# pyboard.net
KiCad netlist of a schematic drawn in Altium Designer
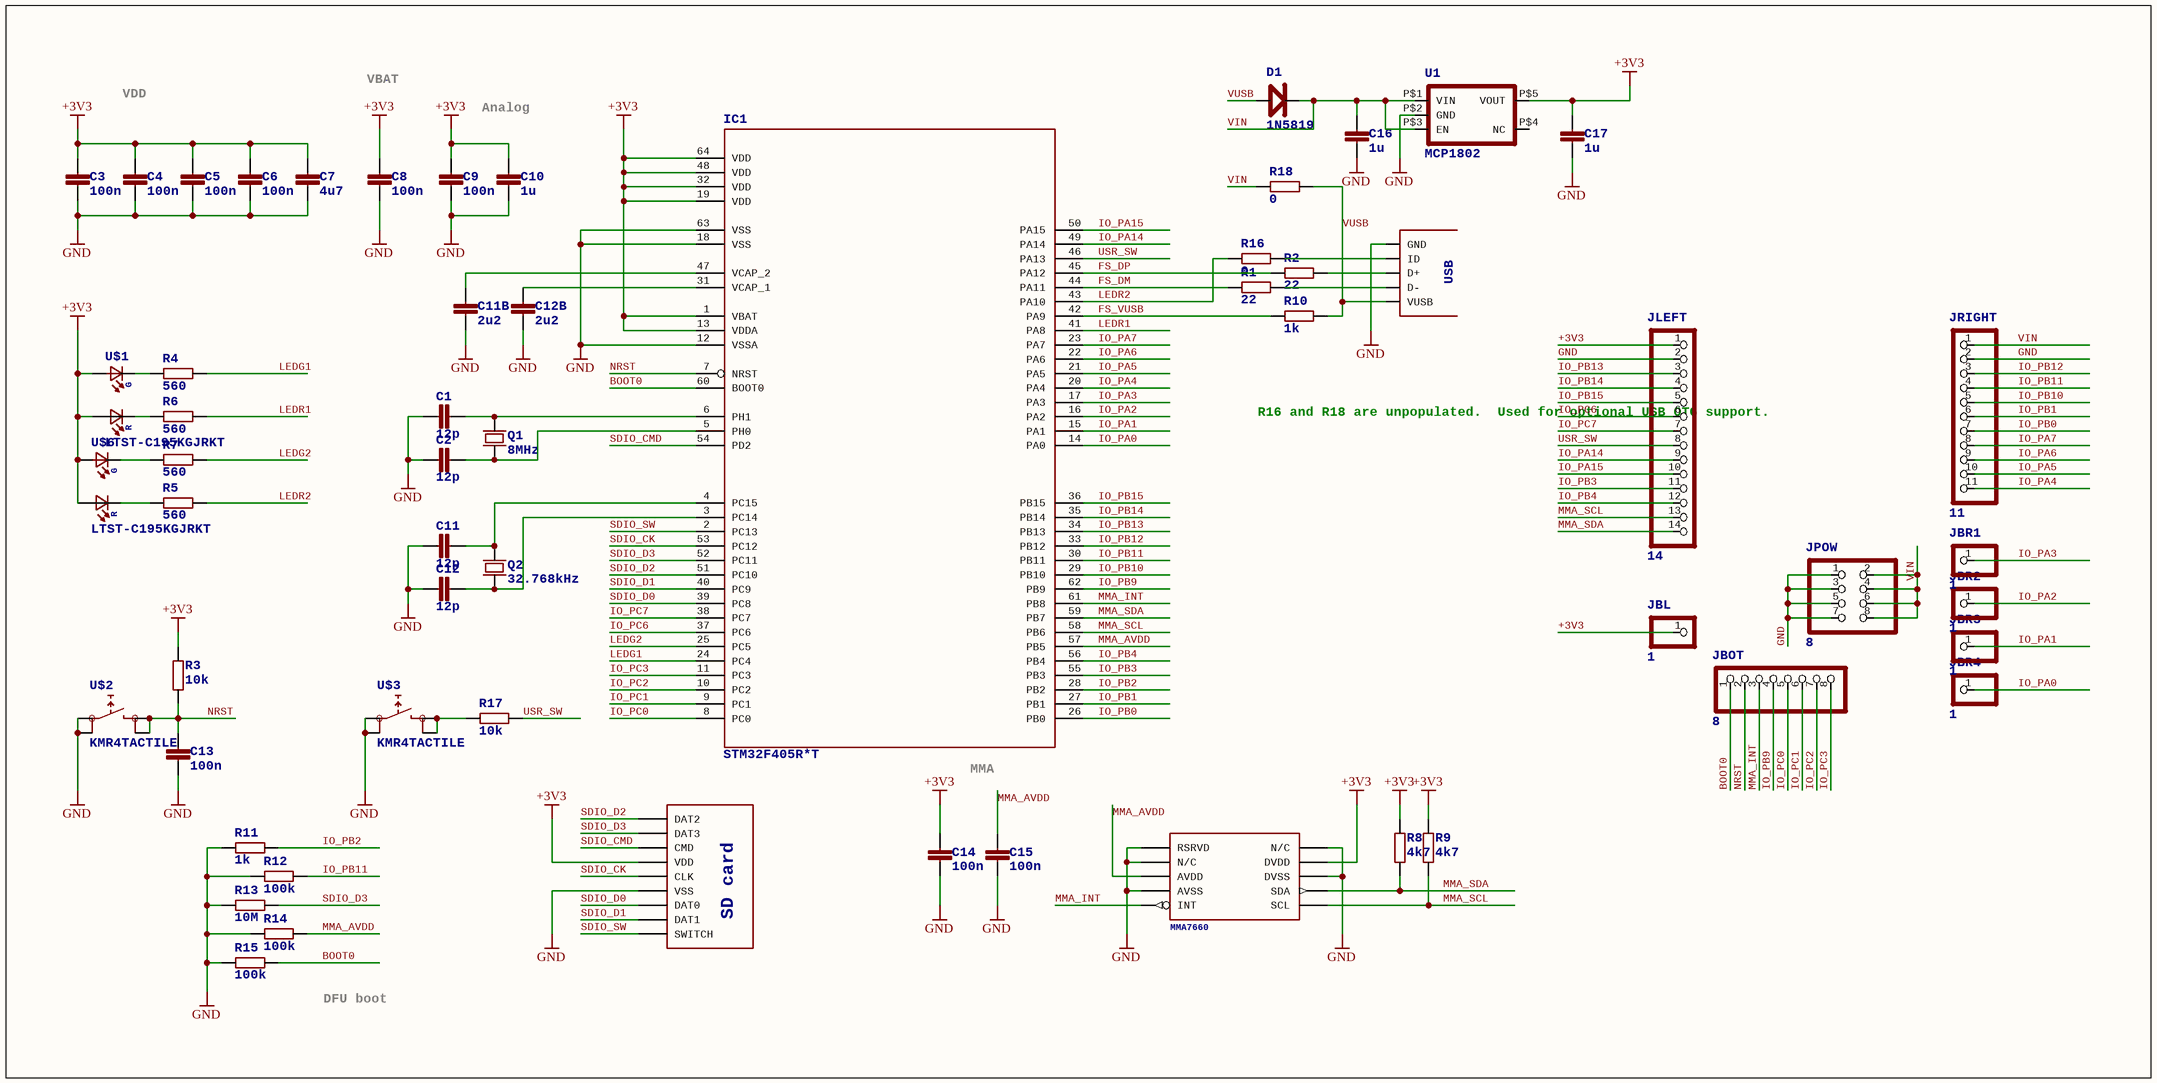
[diagram p0: pyboard.SchDoc]

(export (version "E")
  (design (tool "Eeschema 10.0.6"))
  (components
    (comp (ref "C1")
      (value "12p")
      (footprint "C0603")
      (description "CAPACITOR, European symbol")
      (libsource (lib "") (part "C-EUC0603_1"))
    )
    (comp (ref "C2")
      (value "12p")
      (footprint "C0603")
      (description "CAPACITOR, European symbol")
      (libsource (lib "") (part "C-EUC0603_1"))
    )
    (comp (ref "C3")
      (value "100n")
      (footprint "C0603")
      (description "CAPACITOR, European symbol")
      (libsource (lib "rcl") (part "C-EUC0603"))
    )
    (comp (ref "C4")
      (value "100n")
      (footprint "C0603")
      (description "CAPACITOR, European symbol")
      (libsource (lib "rcl") (part "C-EUC0603"))
    )
    (comp (ref "C5")
      (value "100n")
      (footprint "C0603")
      (description "CAPACITOR, European symbol")
      (libsource (lib "rcl") (part "C-EUC0603"))
    )
    (comp (ref "C6")
      (value "100n")
      (footprint "C0603")
      (description "CAPACITOR, European symbol")
      (libsource (lib "rcl") (part "C-EUC0603"))
    )
    (comp (ref "C7")
      (value "4u7")
      (footprint "C0603")
      (description "CAPACITOR, European symbol")
      (libsource (lib "rcl") (part "C-EUC0603"))
    )
    (comp (ref "C8")
      (value "100n")
      (footprint "C0603")
      (description "CAPACITOR, European symbol")
      (libsource (lib "rcl") (part "C-EUC0603"))
    )
    (comp (ref "C9")
      (value "100n")
      (footprint "C0603")
      (description "CAPACITOR, European symbol")
      (libsource (lib "rcl") (part "C-EUC0603"))
    )
    (comp (ref "C10")
      (value "1u")
      (footprint "C0603")
      (description "CAPACITOR, European symbol")
      (libsource (lib "rcl") (part "C-EUC0603"))
    )
    (comp (ref "C11")
      (value "12p")
      (footprint "C0603")
      (description "CAPACITOR, European symbol")
      (libsource (lib "") (part "C-EUC0603_1"))
    )
    (comp (ref "C11B")
      (value "2u2")
      (footprint "C0603")
      (description "CAPACITOR, European symbol")
      (libsource (lib "rcl") (part "C-EUC0603"))
    )
    (comp (ref "C12")
      (value "12p")
      (footprint "C0603")
      (description "CAPACITOR, European symbol")
      (libsource (lib "") (part "C-EUC0603_1"))
    )
    (comp (ref "C12B")
      (value "2u2")
      (footprint "C0603")
      (description "CAPACITOR, European symbol")
      (libsource (lib "rcl") (part "C-EUC0603"))
    )
    (comp (ref "C13")
      (value "100n")
      (footprint "C0603")
      (description "CAPACITOR, European symbol")
      (libsource (lib "rcl") (part "C-EUC0603"))
    )
    (comp (ref "C14")
      (value "100n")
      (footprint "C0603")
      (description "CAPACITOR, European symbol")
      (libsource (lib "rcl") (part "C-EUC0603"))
    )
    (comp (ref "C15")
      (value "100n")
      (footprint "C0603")
      (description "CAPACITOR, European symbol")
      (libsource (lib "rcl") (part "C-EUC0603"))
    )
    (comp (ref "C16")
      (value "1u")
      (footprint "C0603")
      (description "CAPACITOR, European symbol")
      (libsource (lib "rcl") (part "C-EUC0603"))
    )
    (comp (ref "C17")
      (value "1u")
      (footprint "C0603")
      (description "CAPACITOR, European symbol")
      (libsource (lib "rcl") (part "C-EUC0603"))
    )
    (comp (ref "D1") (value "1N5819") (footprint "SOD-123") (libsource (lib "pyboard") (part "1N5819")))
    (comp (ref "IC1")
      (value "STM32F405R*T")
      (footprint "LQFP64")
      (libsource (lib "pyboard") (part "STM32F405R*T"))
    )
    (comp (ref "JBL")
      (value "1")
      (footprint "1X01")
      (description "PIN HEADER")
      (libsource (lib "pinhead") (part "PINHD-1X1"))
    )
    (comp (ref "JBOT")
      (value "8")
      (footprint "1X08")
      (description "PIN HEADER")
      (libsource (lib "pinhead") (part "PINHD-1X8"))
    )
    (comp (ref "JBR1")
      (value "1")
      (footprint "1X01")
      (description "PIN HEADER")
      (libsource (lib "pinhead") (part "PINHD-1X1"))
    )
    (comp (ref "JBR2")
      (value "1")
      (footprint "1X01")
      (description "PIN HEADER")
      (libsource (lib "pinhead") (part "PINHD-1X1"))
    )
    (comp (ref "JBR3")
      (value "1")
      (footprint "1X01")
      (description "PIN HEADER")
      (libsource (lib "pinhead") (part "PINHD-1X1"))
    )
    (comp (ref "JBR4")
      (value "1")
      (footprint "1X01")
      (description "PIN HEADER")
      (libsource (lib "pinhead") (part "PINHD-1X1"))
    )
    (comp (ref "JLEFT")
      (value "14")
      (footprint "1X14")
      (description "PIN HEADER")
      (libsource (lib "pinhead") (part "PINHD-1X14"))
    )
    (comp (ref "JPOW")
      (value "8")
      (footprint "2X04")
      (description "PIN HEADER")
      (libsource (lib "pinhead") (part "PINHD-2X4"))
    )
    (comp (ref "JRIGHT")
      (value "11")
      (footprint "1X11")
      (description "PIN HEADER")
      (libsource (lib "pinhead") (part "PINHD-1X11"))
    )
    (comp (ref "Q1")
      (value "8MHz")
      (footprint "TXC-SMD-50X32")
      (libsource (lib "pyboard") (part "TXC-CRYSTAL50X32"))
    )
    (comp (ref "Q2")
      (value "32.768kHz")
      (footprint "TXC-SMD-32X15")
      (libsource (lib "pyboard") (part "TXC-CRYSTAL32X15"))
    )
    (comp (ref "R1")
      (value "22")
      (footprint "R0603")
      (description "RESISTOR, European symbol")
      (libsource (lib "rcl") (part "R-EU_R0603"))
    )
    (comp (ref "R2")
      (value "22")
      (footprint "R0603")
      (description "RESISTOR, European symbol")
      (libsource (lib "rcl") (part "R-EU_R0603"))
    )
    (comp (ref "R3")
      (value "10k")
      (footprint "R0603")
      (description "RESISTOR, European symbol")
      (libsource (lib "rcl") (part "R-EU_R0603"))
    )
    (comp (ref "R4")
      (value "560")
      (footprint "R0603")
      (description "RESISTOR, European symbol")
      (libsource (lib "rcl") (part "R-EU_R0603"))
    )
    (comp (ref "R5")
      (value "560")
      (footprint "R0603")
      (description "RESISTOR, European symbol")
      (libsource (lib "rcl") (part "R-EU_R0603"))
    )
    (comp (ref "R6")
      (value "560")
      (footprint "R0603")
      (description "RESISTOR, European symbol")
      (libsource (lib "rcl") (part "R-EU_R0603"))
    )
    (comp (ref "R7")
      (value "560")
      (footprint "R0603")
      (description "RESISTOR, European symbol")
      (libsource (lib "rcl") (part "R-EU_R0603"))
    )
    (comp (ref "R8")
      (value "4k7")
      (footprint "R0603")
      (description "RESISTOR, European symbol")
      (libsource (lib "rcl") (part "R-EU_R0603"))
    )
    (comp (ref "R9")
      (value "4k7")
      (footprint "R0603")
      (description "RESISTOR, European symbol")
      (libsource (lib "rcl") (part "R-EU_R0603"))
    )
    (comp (ref "R10")
      (value "1k")
      (footprint "R0603")
      (description "RESISTOR, European symbol")
      (libsource (lib "rcl") (part "R-EU_R0603"))
    )
    (comp (ref "R11")
      (value "1k")
      (footprint "R0603")
      (description "RESISTOR, European symbol")
      (libsource (lib "rcl") (part "R-EU_R0603"))
    )
    (comp (ref "R12")
      (value "100k")
      (footprint "R0603")
      (description "RESISTOR, European symbol")
      (libsource (lib "rcl") (part "R-EU_R0603"))
    )
    (comp (ref "R13")
      (value "10M")
      (footprint "R0603")
      (description "RESISTOR, European symbol")
      (libsource (lib "rcl") (part "R-EU_R0603"))
    )
    (comp (ref "R14")
      (value "100k")
      (footprint "R0603")
      (description "RESISTOR, European symbol")
      (libsource (lib "rcl") (part "R-EU_R0603"))
    )
    (comp (ref "R15")
      (value "100k")
      (footprint "R0603")
      (description "RESISTOR, European symbol")
      (libsource (lib "rcl") (part "R-EU_R0603"))
    )
    (comp (ref "R16")
      (value "0")
      (footprint "R0603")
      (description "RESISTOR, European symbol")
      (libsource (lib "rcl") (part "R-EU_R0603"))
    )
    (comp (ref "R17")
      (value "10k")
      (footprint "R0603")
      (description "RESISTOR, European symbol")
      (libsource (lib "rcl") (part "R-EU_R0603"))
    )
    (comp (ref "R18")
      (value "0")
      (footprint "R0805")
      (description "RESISTOR, European symbol")
      (libsource (lib "rcl") (part "R-EU_R0805"))
    )
    (comp (ref "U$1")
      (value "LTST-C195KGJRKT")
      (footprint "LTST-BILED-15X16")
      (fields (field (name "R") "R") (field (name "G") "G"))
      (libsource (lib "pyboard") (part "LTST-C195KGJRKT"))
    )
    (comp (ref "U$2")
      (value "KMR4TACTILE")
      (footprint "KMR4SWITCH")
      (libsource (lib "pyboard") (part "KMR4TACTILE"))
    )
    (comp (ref "U$3")
      (value "KMR4TACTILE")
      (footprint "KMR4SWITCH")
      (libsource (lib "pyboard") (part "KMR4TACTILE"))
    )
    (comp (ref "U$4")
      (value "MOLEX-SD-105027")
      (footprint "MOLEX-SD-105027-PKG")
      (fields (field (name "SDCARD") "SD card"))
      (libsource (lib "pyboard") (part "MOLEX-SD-105027"))
    )
    (comp (ref "U$5")
      (value "MMA7660")
      (footprint "DFN10")
      (fields (field (name "MMA7660") "MMA7660"))
      (libsource (lib "pyboard") (part "MMA7660"))
    )
    (comp (ref "U$6")
      (value "LTST-C195KGJRKT")
      (footprint "LTST-BILED-15X16")
      (fields (field (name "R") "R") (field (name "G") "G"))
      (libsource (lib "pyboard") (part "LTST-C195KGJRKT"))
    )
    (comp (ref "U$7")
      (value "USB-MICRO-AB")
      (footprint "HRS-USB-ZX62D-AB-5P8-PKG")
      (fields (field (name "USB") "USB"))
      (libsource (lib "pyboard") (part "USB-MICRO-AB"))
    )
    (comp (ref "U1") (value "MCP1802") (footprint "SOT-23-5") (libsource (lib "pyboard") (part "MCP1802")))
  )
  (nets
    (net (code "1") (name "+3V3") (class "Default")
      (node (ref "C10") (pin "1") (pinfunction "1_1") (pintype "passive"))
      (node (ref "C14") (pin "1") (pinfunction "1_1") (pintype "passive"))
      (node (ref "C17") (pin "1") (pinfunction "1_1") (pintype "passive"))
      (node (ref "C3") (pin "1") (pinfunction "1_1") (pintype "passive"))
      (node (ref "C4") (pin "1") (pinfunction "1_1") (pintype "passive"))
      (node (ref "C5") (pin "1") (pinfunction "1_1") (pintype "passive"))
      (node (ref "C6") (pin "1") (pinfunction "1_1") (pintype "passive"))
      (node (ref "C7") (pin "1") (pinfunction "1_1") (pintype "passive"))
      (node (ref "C8") (pin "1") (pinfunction "1_1") (pintype "passive"))
      (node (ref "C9") (pin "1") (pinfunction "1_1") (pintype "passive"))
      (node (ref "IC1") (pin "1") (pinfunction "VBAT_1") (pintype "power_in"))
      (node (ref "IC1") (pin "13") (pinfunction "VDDA_13") (pintype "power_in"))
      (node (ref "IC1") (pin "19") (pinfunction "VDD_19") (pintype "power_in"))
      (node (ref "IC1") (pin "32") (pinfunction "VDD_32") (pintype "power_in"))
      (node (ref "IC1") (pin "48") (pinfunction "VDD_48") (pintype "power_in"))
      (node (ref "IC1") (pin "64") (pinfunction "VDD_64") (pintype "power_in"))
      (node (ref "JBL") (pin "1") (pinfunction "1_1") (pintype "passive"))
      (node (ref "JLEFT") (pin "1") (pinfunction "1_1") (pintype "passive"))
      (node (ref "R3") (pin "1") (pinfunction "1_1") (pintype "passive"))
      (node (ref "R8") (pin "1") (pinfunction "1_1") (pintype "passive"))
      (node (ref "R9") (pin "1") (pinfunction "1_1") (pintype "passive"))
      (node (ref "U$1") (pin "P$1") (pinfunction "A1_P$1") (pintype "passive"))
      (node (ref "U$1") (pin "P$2") (pinfunction "A2_P$2") (pintype "passive"))
      (node (ref "U$4") (pin "P$4") (pinfunction "VDD_P$4") (pintype "passive"))
      (node (ref "U$5") (pin "P$9") (pinfunction "DVDD_P$9") (pintype "power_in"))
      (node (ref "U$6") (pin "P$1") (pinfunction "A1_P$1") (pintype "passive"))
      (node (ref "U$6") (pin "P$2") (pinfunction "A2_P$2") (pintype "passive"))
      (node (ref "U1") (pin "P$5") (pinfunction "VOUT_P$5") (pintype "power_in"))
    )
    (net (code "2") (name "/BOOT0") (class "Default")
      (node (ref "IC1") (pin "60") (pinfunction "BOOT0_60") (pintype "passive"))
      (node (ref "JBOT") (pin "1") (pinfunction "1_1") (pintype "passive"))
      (node (ref "R15") (pin "1") (pinfunction "1_1") (pintype "passive"))
    )
    (net (code "3") (name "/FS_DM") (class "Default")
      (node (ref "IC1") (pin "44") (pinfunction "PA11_44") (pintype "passive"))
      (node (ref "R1") (pin "2") (pinfunction "2_2") (pintype "passive"))
    )
    (net (code "4") (name "/FS_DP") (class "Default")
      (node (ref "IC1") (pin "45") (pinfunction "PA12_45") (pintype "passive"))
      (node (ref "R2") (pin "2") (pinfunction "2_2") (pintype "passive"))
    )
    (net (code "5") (name "/FS_VUSB") (class "Default")
      (node (ref "IC1") (pin "42") (pinfunction "PA9_42") (pintype "passive"))
      (node (ref "R10") (pin "2") (pinfunction "2_2") (pintype "passive"))
    )
    (net (code "6") (name "/IO_PA0") (class "Default")
      (node (ref "IC1") (pin "14") (pinfunction "PA0_14") (pintype "passive"))
      (node (ref "JBR4") (pin "1") (pinfunction "1_1") (pintype "passive"))
    )
    (net (code "7") (name "/IO_PA1") (class "Default")
      (node (ref "IC1") (pin "15") (pinfunction "PA1_15") (pintype "passive"))
      (node (ref "JBR3") (pin "1") (pinfunction "1_1") (pintype "passive"))
    )
    (net (code "8") (name "/IO_PA2") (class "Default")
      (node (ref "IC1") (pin "16") (pinfunction "PA2_16") (pintype "passive"))
      (node (ref "JBR2") (pin "1") (pinfunction "1_1") (pintype "passive"))
    )
    (net (code "9") (name "/IO_PA3") (class "Default")
      (node (ref "IC1") (pin "17") (pinfunction "PA3_17") (pintype "passive"))
      (node (ref "JBR1") (pin "1") (pinfunction "1_1") (pintype "passive"))
    )
    (net (code "10") (name "/IO_PA4") (class "Default")
      (node (ref "IC1") (pin "20") (pinfunction "PA4_20") (pintype "passive"))
      (node (ref "JRIGHT") (pin "11") (pinfunction "11_11") (pintype "passive"))
    )
    (net (code "11") (name "/IO_PA5") (class "Default")
      (node (ref "IC1") (pin "21") (pinfunction "PA5_21") (pintype "passive"))
      (node (ref "JRIGHT") (pin "10") (pinfunction "10_10") (pintype "passive"))
    )
    (net (code "12") (name "/IO_PA6") (class "Default")
      (node (ref "IC1") (pin "22") (pinfunction "PA6_22") (pintype "passive"))
      (node (ref "JRIGHT") (pin "9") (pinfunction "9_9") (pintype "passive"))
    )
    (net (code "13") (name "/IO_PA7") (class "Default")
      (node (ref "IC1") (pin "23") (pinfunction "PA7_23") (pintype "passive"))
      (node (ref "JRIGHT") (pin "8") (pinfunction "8_8") (pintype "passive"))
    )
    (net (code "14") (name "/IO_PA14") (class "Default")
      (node (ref "IC1") (pin "49") (pinfunction "PA14_49") (pintype "passive"))
      (node (ref "JLEFT") (pin "9") (pinfunction "9_9") (pintype "passive"))
    )
    (net (code "15") (name "/IO_PA15") (class "Default")
      (node (ref "IC1") (pin "50") (pinfunction "PA15_50") (pintype "passive"))
      (node (ref "JLEFT") (pin "10") (pinfunction "10_10") (pintype "passive"))
    )
    (net (code "16") (name "/IO_PB0") (class "Default")
      (node (ref "IC1") (pin "26") (pinfunction "PB0_26") (pintype "passive"))
      (node (ref "JRIGHT") (pin "7") (pinfunction "7_7") (pintype "passive"))
    )
    (net (code "17") (name "/IO_PB1") (class "Default")
      (node (ref "IC1") (pin "27") (pinfunction "PB1_27") (pintype "passive"))
      (node (ref "JRIGHT") (pin "6") (pinfunction "6_6") (pintype "passive"))
    )
    (net (code "18") (name "/IO_PB2") (class "Default")
      (node (ref "IC1") (pin "28") (pinfunction "PB2_28") (pintype "passive"))
      (node (ref "R11") (pin "1") (pinfunction "1_1") (pintype "passive"))
    )
    (net (code "19") (name "/IO_PB3") (class "Default")
      (node (ref "IC1") (pin "55") (pinfunction "PB3_55") (pintype "passive"))
      (node (ref "JLEFT") (pin "11") (pinfunction "11_11") (pintype "passive"))
    )
    (net (code "20") (name "/IO_PB4") (class "Default")
      (node (ref "IC1") (pin "56") (pinfunction "PB4_56") (pintype "passive"))
      (node (ref "JLEFT") (pin "12") (pinfunction "12_12") (pintype "passive"))
    )
    (net (code "21") (name "/IO_PB9") (class "Default")
      (node (ref "IC1") (pin "62") (pinfunction "PB9_62") (pintype "passive"))
      (node (ref "JBOT") (pin "4") (pinfunction "4_4") (pintype "passive"))
    )
    (net (code "22") (name "/IO_PB10") (class "Default")
      (node (ref "IC1") (pin "29") (pinfunction "PB10_29") (pintype "passive"))
      (node (ref "JRIGHT") (pin "5") (pinfunction "5_5") (pintype "passive"))
    )
    (net (code "23") (name "/IO_PB11") (class "Default")
      (node (ref "IC1") (pin "30") (pinfunction "PB11_30") (pintype "passive"))
      (node (ref "JRIGHT") (pin "4") (pinfunction "4_4") (pintype "passive"))
      (node (ref "R12") (pin "1") (pinfunction "1_1") (pintype "passive"))
    )
    (net (code "24") (name "/IO_PB12") (class "Default")
      (node (ref "IC1") (pin "33") (pinfunction "PB12_33") (pintype "passive"))
      (node (ref "JRIGHT") (pin "3") (pinfunction "3_3") (pintype "passive"))
    )
    (net (code "25") (name "/IO_PB13") (class "Default")
      (node (ref "IC1") (pin "34") (pinfunction "PB13_34") (pintype "passive"))
      (node (ref "JLEFT") (pin "3") (pinfunction "3_3") (pintype "passive"))
    )
    (net (code "26") (name "/IO_PB14") (class "Default")
      (node (ref "IC1") (pin "35") (pinfunction "PB14_35") (pintype "passive"))
      (node (ref "JLEFT") (pin "4") (pinfunction "4_4") (pintype "passive"))
    )
    (net (code "27") (name "/IO_PB15") (class "Default")
      (node (ref "IC1") (pin "36") (pinfunction "PB15_36") (pintype "passive"))
      (node (ref "JLEFT") (pin "5") (pinfunction "5_5") (pintype "passive"))
    )
    (net (code "28") (name "/IO_PC0") (class "Default")
      (node (ref "IC1") (pin "8") (pinfunction "PC0_8") (pintype "passive"))
      (node (ref "JBOT") (pin "5") (pinfunction "5_5") (pintype "passive"))
    )
    (net (code "29") (name "/IO_PC1") (class "Default")
      (node (ref "IC1") (pin "9") (pinfunction "PC1_9") (pintype "passive"))
      (node (ref "JBOT") (pin "6") (pinfunction "6_6") (pintype "passive"))
    )
    (net (code "30") (name "/IO_PC2") (class "Default")
      (node (ref "IC1") (pin "10") (pinfunction "PC2_10") (pintype "passive"))
      (node (ref "JBOT") (pin "7") (pinfunction "7_7") (pintype "passive"))
    )
    (net (code "31") (name "/IO_PC3") (class "Default")
      (node (ref "IC1") (pin "11") (pinfunction "PC3_11") (pintype "passive"))
      (node (ref "JBOT") (pin "8") (pinfunction "8_8") (pintype "passive"))
    )
    (net (code "32") (name "/IO_PC6") (class "Default")
      (node (ref "IC1") (pin "37") (pinfunction "PC6_37") (pintype "passive"))
      (node (ref "JLEFT") (pin "6") (pinfunction "6_6") (pintype "passive"))
    )
    (net (code "33") (name "/IO_PC7") (class "Default")
      (node (ref "IC1") (pin "38") (pinfunction "PC7_38") (pintype "passive"))
      (node (ref "JLEFT") (pin "7") (pinfunction "7_7") (pintype "passive"))
    )
    (net (code "34") (name "/LEDG1") (class "Default")
      (node (ref "IC1") (pin "24") (pinfunction "PC4_24") (pintype "passive"))
      (node (ref "R4") (pin "1") (pinfunction "1_1") (pintype "passive"))
    )
    (net (code "35") (name "/LEDG2") (class "Default")
      (node (ref "IC1") (pin "25") (pinfunction "PC5_25") (pintype "passive"))
      (node (ref "R7") (pin "1") (pinfunction "1_1") (pintype "passive"))
    )
    (net (code "36") (name "/LEDR1") (class "Default")
      (node (ref "IC1") (pin "41") (pinfunction "PA8_41") (pintype "passive"))
      (node (ref "R6") (pin "1") (pinfunction "1_1") (pintype "passive"))
    )
    (net (code "37") (name "/LEDR2") (class "Default")
      (node (ref "IC1") (pin "43") (pinfunction "PA10_43") (pintype "passive"))
      (node (ref "R16") (pin "2") (pinfunction "2_2") (pintype "passive"))
      (node (ref "R5") (pin "1") (pinfunction "1_1") (pintype "passive"))
    )
    (net (code "38") (name "/MMA_AVDD") (class "Default")
      (node (ref "C15") (pin "1") (pinfunction "1_1") (pintype "passive"))
      (node (ref "IC1") (pin "57") (pinfunction "PB5_57") (pintype "passive"))
      (node (ref "R14") (pin "1") (pinfunction "1_1") (pintype "passive"))
      (node (ref "U$5") (pin "P$3") (pinfunction "AVDD_P$3") (pintype "power_in"))
    )
    (net (code "39") (name "/MMA_INT") (class "Default")
      (node (ref "IC1") (pin "61") (pinfunction "PB8_61") (pintype "passive"))
      (node (ref "JBOT") (pin "3") (pinfunction "3_3") (pintype "passive"))
      (node (ref "U$5") (pin "P$5") (pinfunction "INT_P$5") (pintype "output"))
    )
    (net (code "40") (name "/MMA_SCL") (class "Default")
      (node (ref "IC1") (pin "58") (pinfunction "PB6_58") (pintype "passive"))
      (node (ref "JLEFT") (pin "13") (pinfunction "13_13") (pintype "passive"))
      (node (ref "R9") (pin "2") (pinfunction "2_2") (pintype "passive"))
      (node (ref "U$5") (pin "P$6") (pinfunction "SCL_P$6") (pintype "passive"))
    )
    (net (code "41") (name "/MMA_SDA") (class "Default")
      (node (ref "IC1") (pin "59") (pinfunction "PB7_59") (pintype "passive"))
      (node (ref "JLEFT") (pin "14") (pinfunction "14_14") (pintype "passive"))
      (node (ref "R8") (pin "2") (pinfunction "2_2") (pintype "passive"))
      (node (ref "U$5") (pin "P$7") (pinfunction "SDA_P$7") (pintype "output"))
    )
    (net (code "42") (name "/NRST") (class "Default")
      (node (ref "C13") (pin "1") (pinfunction "1_1") (pintype "passive"))
      (node (ref "IC1") (pin "7") (pinfunction "NRST_7") (pintype "passive"))
      (node (ref "JBOT") (pin "2") (pinfunction "2_2") (pintype "passive"))
      (node (ref "R3") (pin "2") (pinfunction "2_2") (pintype "passive"))
      (node (ref "U$2") (pin "P$3") (pinfunction "1_P$3") (pintype "passive"))
      (node (ref "U$2") (pin "P$4") (pinfunction "1_P$4") (pintype "passive"))
    )
    (net (code "43") (name "/SDIO_CK") (class "Default")
      (node (ref "IC1") (pin "53") (pinfunction "PC12_53") (pintype "passive"))
      (node (ref "U$4") (pin "P$5") (pinfunction "CLK_P$5") (pintype "passive"))
    )
    (net (code "44") (name "/SDIO_CMD") (class "Default")
      (node (ref "IC1") (pin "54") (pinfunction "PD2_54") (pintype "passive"))
      (node (ref "U$4") (pin "P$3") (pinfunction "CMD_P$3") (pintype "passive"))
    )
    (net (code "45") (name "/SDIO_D0") (class "Default")
      (node (ref "IC1") (pin "39") (pinfunction "PC8_39") (pintype "passive"))
      (node (ref "U$4") (pin "P$7") (pinfunction "DAT0_P$7") (pintype "passive"))
    )
    (net (code "46") (name "/SDIO_D1") (class "Default")
      (node (ref "IC1") (pin "40") (pinfunction "PC9_40") (pintype "passive"))
      (node (ref "U$4") (pin "P$8") (pinfunction "DAT1_P$8") (pintype "passive"))
    )
    (net (code "47") (name "/SDIO_D2") (class "Default")
      (node (ref "IC1") (pin "51") (pinfunction "PC10_51") (pintype "passive"))
      (node (ref "U$4") (pin "P$1") (pinfunction "DAT2_P$1") (pintype "passive"))
    )
    (net (code "48") (name "/SDIO_D3") (class "Default")
      (node (ref "IC1") (pin "52") (pinfunction "PC11_52") (pintype "passive"))
      (node (ref "R13") (pin "1") (pinfunction "1_1") (pintype "passive"))
      (node (ref "U$4") (pin "P$2") (pinfunction "DAT3_P$2") (pintype "passive"))
    )
    (net (code "49") (name "/SDIO_SW") (class "Default")
      (node (ref "IC1") (pin "2") (pinfunction "PC13_2") (pintype "passive"))
      (node (ref "U$4") (pin "G$1") (pinfunction "SWITCH_G$1") (pintype "passive"))
    )
    (net (code "50") (name "/USR_SW") (class "Default")
      (node (ref "IC1") (pin "46") (pinfunction "PA13_46") (pintype "passive"))
      (node (ref "JLEFT") (pin "8") (pinfunction "8_8") (pintype "passive"))
      (node (ref "R17") (pin "1") (pinfunction "1_1") (pintype "passive"))
    )
    (net (code "51") (name "/VIN") (class "Default")
      (node (ref "C16") (pin "1") (pinfunction "1_1") (pintype "passive"))
      (node (ref "D1") (pin "K") (pinfunction "K_K") (pintype "passive"))
      (node (ref "JPOW") (pin "2") (pinfunction "2_2") (pintype "passive"))
      (node (ref "JPOW") (pin "4") (pinfunction "4_4") (pintype "passive"))
      (node (ref "JPOW") (pin "6") (pinfunction "6_6") (pintype "passive"))
      (node (ref "JPOW") (pin "8") (pinfunction "8_8") (pintype "passive"))
      (node (ref "JRIGHT") (pin "1") (pinfunction "1_1") (pintype "passive"))
      (node (ref "R18") (pin "1") (pinfunction "1_1") (pintype "passive"))
      (node (ref "U1") (pin "P$1") (pinfunction "VIN_P$1") (pintype "power_in"))
      (node (ref "U1") (pin "P$3") (pinfunction "EN_P$3") (pintype "passive"))
    )
    (net (code "52") (name "/VUSB") (class "Default")
      (node (ref "D1") (pin "A") (pinfunction "A_A") (pintype "passive"))
      (node (ref "R10") (pin "1") (pinfunction "1_1") (pintype "passive"))
      (node (ref "R18") (pin "2") (pinfunction "2_2") (pintype "passive"))
      (node (ref "U$7") (pin "P$1") (pinfunction "VUSB_P$1") (pintype "power_in"))
    )
    (net (code "53") (name "GND") (class "Default")
      (node (ref "C1") (pin "1") (pinfunction "1_1") (pintype "passive"))
      (node (ref "C10") (pin "2") (pinfunction "2_2") (pintype "passive"))
      (node (ref "C11") (pin "1") (pinfunction "1_1") (pintype "passive"))
      (node (ref "C11B") (pin "2") (pinfunction "2_2") (pintype "passive"))
      (node (ref "C12") (pin "1") (pinfunction "1_1") (pintype "passive"))
      (node (ref "C12B") (pin "2") (pinfunction "2_2") (pintype "passive"))
      (node (ref "C13") (pin "2") (pinfunction "2_2") (pintype "passive"))
      (node (ref "C14") (pin "2") (pinfunction "2_2") (pintype "passive"))
      (node (ref "C15") (pin "2") (pinfunction "2_2") (pintype "passive"))
      (node (ref "C16") (pin "2") (pinfunction "2_2") (pintype "passive"))
      (node (ref "C17") (pin "2") (pinfunction "2_2") (pintype "passive"))
      (node (ref "C2") (pin "1") (pinfunction "1_1") (pintype "passive"))
      (node (ref "C3") (pin "2") (pinfunction "2_2") (pintype "passive"))
      (node (ref "C4") (pin "2") (pinfunction "2_2") (pintype "passive"))
      (node (ref "C5") (pin "2") (pinfunction "2_2") (pintype "passive"))
      (node (ref "C6") (pin "2") (pinfunction "2_2") (pintype "passive"))
      (node (ref "C7") (pin "2") (pinfunction "2_2") (pintype "passive"))
      (node (ref "C8") (pin "2") (pinfunction "2_2") (pintype "passive"))
      (node (ref "C9") (pin "2") (pinfunction "2_2") (pintype "passive"))
      (node (ref "IC1") (pin "12") (pinfunction "VSSA_12") (pintype "power_in"))
      (node (ref "IC1") (pin "18") (pinfunction "VSS_18") (pintype "power_in"))
      (node (ref "IC1") (pin "63") (pinfunction "VSS_63") (pintype "power_in"))
      (node (ref "JLEFT") (pin "2") (pinfunction "2_2") (pintype "passive"))
      (node (ref "JPOW") (pin "1") (pinfunction "1_1") (pintype "passive"))
      (node (ref "JPOW") (pin "3") (pinfunction "3_3") (pintype "passive"))
      (node (ref "JPOW") (pin "5") (pinfunction "5_5") (pintype "passive"))
      (node (ref "JPOW") (pin "7") (pinfunction "7_7") (pintype "passive"))
      (node (ref "JRIGHT") (pin "2") (pinfunction "2_2") (pintype "passive"))
      (node (ref "R11") (pin "2") (pinfunction "2_2") (pintype "passive"))
      (node (ref "R12") (pin "2") (pinfunction "2_2") (pintype "passive"))
      (node (ref "R13") (pin "2") (pinfunction "2_2") (pintype "passive"))
      (node (ref "R14") (pin "2") (pinfunction "2_2") (pintype "passive"))
      (node (ref "R15") (pin "2") (pinfunction "2_2") (pintype "passive"))
      (node (ref "U$2") (pin "P$1") (pinfunction "0_P$1") (pintype "passive"))
      (node (ref "U$2") (pin "P$2") (pinfunction "0_P$2") (pintype "passive"))
      (node (ref "U$3") (pin "P$1") (pinfunction "0_P$1") (pintype "passive"))
      (node (ref "U$3") (pin "P$2") (pinfunction "0_P$2") (pintype "passive"))
      (node (ref "U$4") (pin "P$6") (pinfunction "VSS_P$6") (pintype "passive"))
      (node (ref "U$5") (pin "P$1") (pinfunction "RSRVD_P$1") (pintype "passive"))
      (node (ref "U$5") (pin "P$10") (pinfunction "N/C_P$10") (pintype "passive"))
      (node (ref "U$5") (pin "P$2") (pinfunction "N/C_P$2") (pintype "passive"))
      (node (ref "U$5") (pin "P$4") (pinfunction "AVSS_P$4") (pintype "power_in"))
      (node (ref "U$5") (pin "P$8") (pinfunction "DVSS_P$8") (pintype "power_in"))
      (node (ref "U$7") (pin "P$5") (pinfunction "GND_P$5") (pintype "power_in"))
      (node (ref "U1") (pin "P$2") (pinfunction "GND_P$2") (pintype "power_in"))
    )
    (net (code "54") (name "Net-(IC1-PC14)") (class "Default")
      (node (ref "C12") (pin "2") (pinfunction "2_2") (pintype "passive"))
      (node (ref "IC1") (pin "3") (pinfunction "PC14_3") (pintype "passive"))
      (node (ref "Q2") (pin "P$1") (pinfunction "P$1_P$1") (pintype "passive"))
    )
    (net (code "55") (name "Net-(IC1-PC15)") (class "Default")
      (node (ref "C11") (pin "2") (pinfunction "2_2") (pintype "passive"))
      (node (ref "IC1") (pin "4") (pinfunction "PC15_4") (pintype "passive"))
      (node (ref "Q2") (pin "P$2") (pinfunction "P$2_P$2") (pintype "passive"))
    )
    (net (code "56") (name "Net-(IC1-PH0)") (class "Default")
      (node (ref "C2") (pin "2") (pinfunction "2_2") (pintype "passive"))
      (node (ref "IC1") (pin "5") (pinfunction "PH0_5") (pintype "passive"))
      (node (ref "Q1") (pin "P$1") (pinfunction "P$1_P$1") (pintype "passive"))
    )
    (net (code "57") (name "Net-(IC1-PH1)") (class "Default")
      (node (ref "C1") (pin "2") (pinfunction "2_2") (pintype "passive"))
      (node (ref "IC1") (pin "6") (pinfunction "PH1_6") (pintype "passive"))
      (node (ref "Q1") (pin "P$2") (pinfunction "P$2_P$2") (pintype "passive"))
    )
    (net (code "58") (name "Net-(IC1-VCAP_1)") (class "Default")
      (node (ref "C12B") (pin "1") (pinfunction "1_1") (pintype "passive"))
      (node (ref "IC1") (pin "31") (pinfunction "VCAP_1_31") (pintype "passive"))
    )
    (net (code "59") (name "Net-(IC1-VCAP_2)") (class "Default")
      (node (ref "C11B") (pin "1") (pinfunction "1_1") (pintype "passive"))
      (node (ref "IC1") (pin "47") (pinfunction "VCAP_2_47") (pintype "passive"))
    )
    (net (code "60") (name "Net-(R17-Pad2)") (class "Default")
      (node (ref "R17") (pin "2") (pinfunction "2_2") (pintype "passive"))
      (node (ref "U$3") (pin "P$3") (pinfunction "1_P$3") (pintype "passive"))
      (node (ref "U$3") (pin "P$4") (pinfunction "1_P$4") (pintype "passive"))
    )
    (net (code "61") (name "Net-(U$1-K1)") (class "Default")
      (node (ref "R4") (pin "2") (pinfunction "2_2") (pintype "passive"))
      (node (ref "U$1") (pin "P$3") (pinfunction "K1_P$3") (pintype "passive"))
    )
    (net (code "62") (name "Net-(U$1-K2)") (class "Default")
      (node (ref "R6") (pin "2") (pinfunction "2_2") (pintype "passive"))
      (node (ref "U$1") (pin "P$4") (pinfunction "K2_P$4") (pintype "passive"))
    )
    (net (code "63") (name "Net-(U$6-K1)") (class "Default")
      (node (ref "R7") (pin "2") (pinfunction "2_2") (pintype "passive"))
      (node (ref "U$6") (pin "P$3") (pinfunction "K1_P$3") (pintype "passive"))
    )
    (net (code "64") (name "Net-(U$6-K2)") (class "Default")
      (node (ref "R5") (pin "2") (pinfunction "2_2") (pintype "passive"))
      (node (ref "U$6") (pin "P$4") (pinfunction "K2_P$4") (pintype "passive"))
    )
    (net (code "65") (name "Net-(U$7-D+)") (class "Default")
      (node (ref "R2") (pin "1") (pinfunction "1_1") (pintype "passive"))
      (node (ref "U$7") (pin "P$3") (pinfunction "D+_P$3") (pintype "passive"))
    )
    (net (code "66") (name "Net-(U$7-D-)") (class "Default")
      (node (ref "R1") (pin "1") (pinfunction "1_1") (pintype "passive"))
      (node (ref "U$7") (pin "P$2") (pinfunction "D-_P$2") (pintype "passive"))
    )
    (net (code "67") (name "Net-(U$7-ID)") (class "Default")
      (node (ref "R16") (pin "1") (pinfunction "1_1") (pintype "passive"))
      (node (ref "U$7") (pin "P$4") (pinfunction "ID_P$4") (pintype "passive"))
    )
    (net (code "68") (name "unconnected-(U1-NC-PadP$4)") (class "Default")
      (node (ref "U1") (pin "P$4") (pinfunction "NC_P$4") (pintype "passive"))
    )
  )
)
